# Fog_DRL_Cam.net
KiCad netlist of a schematic drawn in EAGLE
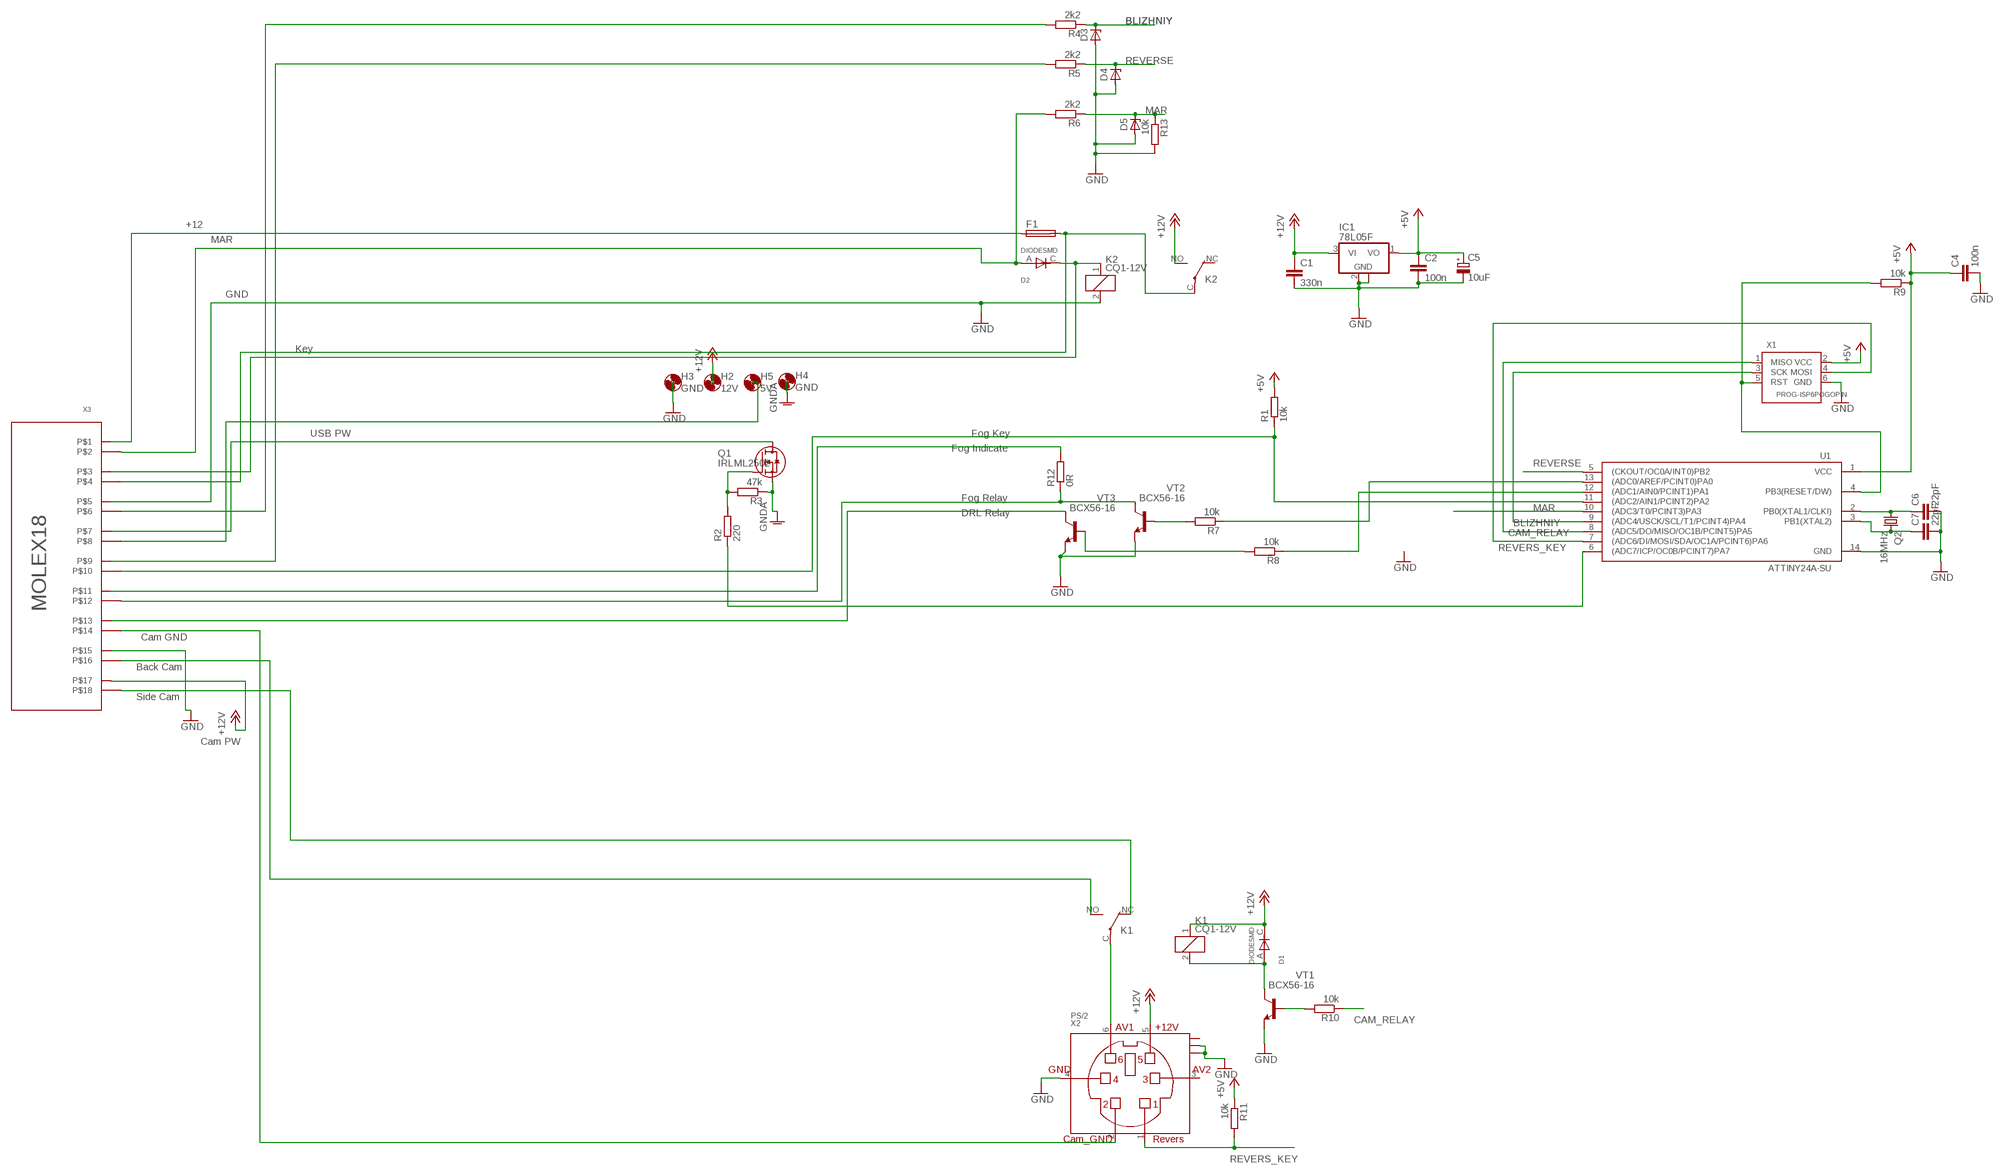
[diagram p0: schematic, sheet 1]

(export (version "E")
  (design (tool "Eeschema 10.0.6"))
  (components
    (comp (ref "C1")
      (value "330n")
      (footprint "eagle-import:C0805")
      (libsource (lib "eagle-import") (part "C-EUC0805"))
    )
    (comp (ref "C2")
      (value "100n")
      (footprint "eagle-import:C0603")
      (libsource (lib "eagle-import") (part "C-EUC0603"))
    )
    (comp (ref "C4")
      (value "100n")
      (footprint "eagle-import:C0603")
      (libsource (lib "eagle-import") (part "C-EUC0603"))
    )
    (comp (ref "C5")
      (value "10uF")
      (footprint "eagle-import:CT3216")
      (libsource (lib "eagle-import") (part "CPOL-EUCT3216"))
    )
    (comp (ref "C6")
      (value "22pF")
      (footprint "eagle-import:C0603")
      (libsource (lib "eagle-import") (part "rcl_334_C-EUC0603"))
    )
    (comp (ref "C7")
      (value "22pF")
      (footprint "eagle-import:C0603")
      (libsource (lib "eagle-import") (part "rcl_334_C-EUC0603"))
    )
    (comp (ref "D1")
      (value "DIODESMD")
      (footprint "eagle-import:DO214AC")
      (libsource (lib "eagle-import") (part "DIODESMD"))
    )
    (comp (ref "D2")
      (value "DIODESMD")
      (footprint "eagle-import:DO214AC")
      (libsource (lib "eagle-import") (part "DIODESMD"))
    )
    (comp (ref "D3")
      (value "ZENER-DIODESOD80C")
      (footprint "eagle-import:SOD80C")
      (libsource (lib "eagle-import") (part "ZENER-DIODESOD80C"))
    )
    (comp (ref "D4")
      (value "ZENER-DIODESOD80C")
      (footprint "eagle-import:SOD80C")
      (libsource (lib "eagle-import") (part "ZENER-DIODESOD80C"))
    )
    (comp (ref "D5")
      (value "ZENER-DIODESOD80C")
      (footprint "eagle-import:SOD80C")
      (libsource (lib "eagle-import") (part "ZENER-DIODESOD80C"))
    )
    (comp (ref "F1")
      (value "SH22,5A")
      (footprint "eagle-import:SH22,5A")
      (fields (field (name "MPN") "0031.7701.11"))
      (libsource (lib "eagle-import") (part "SH22,5A"))
    )
    (comp (ref "H2")
      (value "12V")
      (footprint "eagle-import:3,0")
      (libsource (lib "eagle-import") (part "MOUNT-HOLE3.0"))
    )
    (comp (ref "H3")
      (value "GND")
      (footprint "eagle-import:3,0")
      (libsource (lib "eagle-import") (part "MOUNT-HOLE3.0"))
    )
    (comp (ref "H4")
      (value "GND")
      (footprint "eagle-import:3,0")
      (libsource (lib "eagle-import") (part "MOUNT-HOLE3.0"))
    )
    (comp (ref "H5")
      (value "5V")
      (footprint "eagle-import:3,0")
      (libsource (lib "eagle-import") (part "MOUNT-HOLE3.0"))
    )
    (comp (ref "IC1")
      (value "78L05F")
      (footprint "eagle-import:SOT89")
      (libsource (lib "eagle-import") (part "78LF05"))
    )
    (comp (ref "K1")
      (value "CQ1-12V")
      (footprint "eagle-import:CQ1")
      (libsource (lib "eagle-import") (part "CQ1-12V"))
    )
    (comp (ref "K2")
      (value "CQ1-12V")
      (footprint "eagle-import:CQ1")
      (libsource (lib "eagle-import") (part "CQ1-12V"))
    )
    (comp (ref "Q1")
      (value "IRLML2502")
      (footprint "eagle-import:SOT-23-GSD")
      (libsource (lib "eagle-import") (part "SI2302"))
    )
    (comp (ref "Q2")
      (value "16MHz")
      (footprint "eagle-import:HC49_S")
      (libsource (lib "eagle-import") (part "CRYSTALHC49S"))
    )
    (comp (ref "R1")
      (value "10k")
      (footprint "eagle-import:R0603")
      (libsource (lib "eagle-import") (part "R-EU_R0603"))
    )
    (comp (ref "R2")
      (value "220")
      (footprint "eagle-import:R0603")
      (libsource (lib "eagle-import") (part "R-EU_R0603"))
    )
    (comp (ref "R3")
      (value "47k")
      (footprint "eagle-import:R0603")
      (libsource (lib "eagle-import") (part "R-EU_R0603"))
    )
    (comp (ref "R4")
      (value "2k2")
      (footprint "eagle-import:R0603")
      (libsource (lib "eagle-import") (part "R-EU_R0603"))
    )
    (comp (ref "R5")
      (value "2k2")
      (footprint "eagle-import:R0603")
      (libsource (lib "eagle-import") (part "R-EU_R0603"))
    )
    (comp (ref "R6")
      (value "2k2")
      (footprint "eagle-import:R0603")
      (libsource (lib "eagle-import") (part "R-EU_R0603"))
    )
    (comp (ref "R7")
      (value "10k")
      (footprint "eagle-import:R0603")
      (libsource (lib "eagle-import") (part "R-EU_R0603"))
    )
    (comp (ref "R8")
      (value "10k")
      (footprint "eagle-import:R0603")
      (libsource (lib "eagle-import") (part "R-EU_R0603"))
    )
    (comp (ref "R9")
      (value "10k")
      (footprint "eagle-import:R0603")
      (libsource (lib "eagle-import") (part "R-EU_R0603"))
    )
    (comp (ref "R10")
      (value "10k")
      (footprint "eagle-import:R0603")
      (libsource (lib "eagle-import") (part "R-EU_R0603"))
    )
    (comp (ref "R11")
      (value "10k")
      (footprint "eagle-import:R0603")
      (libsource (lib "eagle-import") (part "R-EU_R0603"))
    )
    (comp (ref "R12")
      (value "0R")
      (footprint "eagle-import:R0603")
      (libsource (lib "eagle-import") (part "R-EU_R0603"))
    )
    (comp (ref "R13")
      (value "10k")
      (footprint "eagle-import:R0603")
      (libsource (lib "eagle-import") (part "R-EU_R0603"))
    )
    (comp (ref "U1")
      (value "ATTINY24A-SU")
      (footprint "eagle-import:SO14")
      (libsource (lib "eagle-import") (part "ATTINY24A-SU"))
    )
    (comp (ref "VT1")
      (value "BCX56-16")
      (footprint "eagle-import:SOT89-BCE")
      (libsource (lib "eagle-import") (part "BCX56-16"))
    )
    (comp (ref "VT2")
      (value "BCX56-16")
      (footprint "eagle-import:SOT89-BCE")
      (libsource (lib "eagle-import") (part "BCX56-16"))
    )
    (comp (ref "VT3")
      (value "BCX56-16")
      (footprint "eagle-import:SOT89-BCE")
      (libsource (lib "eagle-import") (part "BCX56-16"))
    )
    (comp (ref "X1")
      (value "PROG-ISP6POGOPIN")
      (footprint "eagle-import:PROG_POGOPIN")
      (libsource (lib "eagle-import") (part "PROG-ISP6POGOPIN"))
    )
    (comp (ref "X2")
      (value "PS/2")
      (footprint "eagle-import:PS_2")
      (libsource (lib "eagle-import") (part "PS/2"))
    )
    (comp (ref "X3")
      (value "MOLEX18")
      (footprint "eagle-import:MOLEX18")
      (libsource (lib "eagle-import") (part "MOLEX18"))
    )
  )
  (nets
    (net (code "1") (name "+5V") (class "Default")
      (node (ref "C2") (pin "1") (pinfunction "1_1") (pintype "passive"))
      (node (ref "C4") (pin "1") (pinfunction "1_1") (pintype "passive"))
      (node (ref "C5") (pin "+") (pinfunction "+_+") (pintype "passive"))
      (node (ref "IC1") (pin "1") (pinfunction "VO_1") (pintype "passive"))
      (node (ref "R1") (pin "2") (pinfunction "2_2") (pintype "passive"))
      (node (ref "R11") (pin "1") (pinfunction "1_1") (pintype "passive"))
      (node (ref "R9") (pin "1") (pinfunction "1_1") (pintype "passive"))
      (node (ref "U1") (pin "1") (pinfunction "VCC_1") (pintype "power_in"))
      (node (ref "X1") (pin "2") (pinfunction "VCC_2") (pintype "bidirectional"))
    )
    (net (code "2") (name "+12V") (class "Default")
      (node (ref "C1") (pin "1") (pinfunction "1_1") (pintype "passive"))
      (node (ref "D1") (pin "C") (pinfunction "KATOD_C") (pintype "power_in"))
      (node (ref "H2") (pin "P$1") (pinfunction "P$1_P$1") (pintype "bidirectional"))
      (node (ref "IC1") (pin "3") (pinfunction "VI_3") (pintype "input"))
      (node (ref "K1") (pin "1") (pinfunction "1_1") (pintype "passive"))
      (node (ref "K2") (pin "NO") (pinfunction "S_NO") (pintype "passive"))
      (node (ref "X2") (pin "5") (pinfunction "5_5") (pintype "bidirectional"))
      (node (ref "X3") (pin "P$17") (pinfunction "P$17_P$17") (pintype "bidirectional"))
    )
    (net (code "3") (name "/BLIZHNIY") (class "Default")
      (node (ref "D3") (pin "C") (pinfunction "C_C") (pintype "passive"))
      (node (ref "R4") (pin "1") (pinfunction "1_1") (pintype "passive"))
      (node (ref "U1") (pin "9") (pinfunction "(ADC4/USCK/SCL/T1/PCINT4)PA4_9") (pintype "bidirectional"))
      (node (ref "X1") (pin "3") (pinfunction "SCK_3") (pintype "bidirectional"))
    )
    (net (code "4") (name "/CAM_RELAY") (class "Default")
      (node (ref "R10") (pin "1") (pinfunction "1_1") (pintype "passive"))
      (node (ref "U1") (pin "8") (pinfunction "(ADC5/DO/MISO/OC1B/PCINT5)PA5_8") (pintype "bidirectional"))
      (node (ref "X1") (pin "1") (pinfunction "MISO_1") (pintype "bidirectional"))
    )
    (net (code "5") (name "/MAR") (class "Default")
      (node (ref "D5") (pin "C") (pinfunction "C_C") (pintype "passive"))
      (node (ref "R13") (pin "1") (pinfunction "1_1") (pintype "passive"))
      (node (ref "R6") (pin "1") (pinfunction "1_1") (pintype "passive"))
      (node (ref "U1") (pin "10") (pinfunction "(ADC3/T0/PCINT3)PA3_10") (pintype "bidirectional"))
    )
    (net (code "6") (name "/REVERSE") (class "Default")
      (node (ref "D4") (pin "C") (pinfunction "C_C") (pintype "passive"))
      (node (ref "R5") (pin "1") (pinfunction "1_1") (pintype "passive"))
      (node (ref "U1") (pin "5") (pinfunction "(CKOUT/OC0A/INT0)PB2_5") (pintype "bidirectional"))
    )
    (net (code "7") (name "/REVERS_KEY") (class "Default")
      (node (ref "R11") (pin "2") (pinfunction "2_2") (pintype "passive"))
      (node (ref "U1") (pin "7") (pinfunction "(ADC6/DI/MOSI/SDA/OC1A/PCINT6)PA6_7") (pintype "bidirectional"))
      (node (ref "X1") (pin "4") (pinfunction "MOSI_4") (pintype "bidirectional"))
      (node (ref "X2") (pin "1") (pinfunction "1_1") (pintype "bidirectional"))
    )
    (net (code "8") (name "GND") (class "Default")
      (node (ref "C1") (pin "2") (pinfunction "2_2") (pintype "passive"))
      (node (ref "C2") (pin "2") (pinfunction "2_2") (pintype "passive"))
      (node (ref "C4") (pin "2") (pinfunction "2_2") (pintype "passive"))
      (node (ref "C5") (pin "-") (pinfunction "-_-") (pintype "passive"))
      (node (ref "C6") (pin "2") (pinfunction "2_2") (pintype "passive"))
      (node (ref "C7") (pin "2") (pinfunction "2_2") (pintype "passive"))
      (node (ref "D3") (pin "A") (pinfunction "A_A") (pintype "passive"))
      (node (ref "D4") (pin "A") (pinfunction "A_A") (pintype "passive"))
      (node (ref "D5") (pin "A") (pinfunction "A_A") (pintype "passive"))
      (node (ref "H3") (pin "P$1") (pinfunction "P$1_P$1") (pintype "bidirectional"))
      (node (ref "IC1") (pin "2") (pinfunction "GND_2") (pintype "passive"))
      (node (ref "IC1") (pin "2@1") (pinfunction "GND_2@1") (pintype "passive"))
      (node (ref "K2") (pin "2") (pinfunction "2_2") (pintype "passive"))
      (node (ref "R13") (pin "2") (pinfunction "2_2") (pintype "passive"))
      (node (ref "U1") (pin "14") (pinfunction "GND_14") (pintype "power_in"))
      (node (ref "VT1") (pin "E") (pinfunction "E_E") (pintype "passive"))
      (node (ref "VT2") (pin "E") (pinfunction "E_E") (pintype "passive"))
      (node (ref "VT3") (pin "E") (pinfunction "E_E") (pintype "passive"))
      (node (ref "X1") (pin "6") (pinfunction "GND_6") (pintype "power_in"))
      (node (ref "X2") (pin "4") (pinfunction "4_4") (pintype "bidirectional"))
      (node (ref "X2") (pin "GND0") (pinfunction "GND0_GND0") (pintype "bidirectional"))
      (node (ref "X2") (pin "GND2") (pinfunction "GND2_GND2") (pintype "bidirectional"))
      (node (ref "X3") (pin "P$15") (pinfunction "P$15_P$15") (pintype "bidirectional"))
      (node (ref "X3") (pin "P$5") (pinfunction "P$5_P$5") (pintype "bidirectional"))
    )
    (net (code "9") (name "GNDA") (class "Default")
      (node (ref "H4") (pin "P$1") (pinfunction "P$1_P$1") (pintype "bidirectional"))
      (node (ref "Q1") (pin "S") (pinfunction "S_S") (pintype "passive"))
      (node (ref "R3") (pin "1") (pinfunction "1_1") (pintype "passive"))
    )
    (net (code "10") (name "Net-(D1-ANOD)") (class "Default")
      (node (ref "D1") (pin "A") (pinfunction "ANOD_A") (pintype "power_in"))
      (node (ref "K1") (pin "2") (pinfunction "2_2") (pintype "passive"))
      (node (ref "VT1") (pin "C") (pinfunction "C_C") (pintype "passive"))
      (node (ref "VT1") (pin "C@1") (pinfunction "C_C@1") (pintype "passive"))
    )
    (net (code "11") (name "Net-(D2-ANOD)") (class "Default")
      (node (ref "D2") (pin "A") (pinfunction "ANOD_A") (pintype "power_in"))
      (node (ref "R6") (pin "2") (pinfunction "2_2") (pintype "passive"))
      (node (ref "X3") (pin "P$2") (pinfunction "P$2_P$2") (pintype "bidirectional"))
    )
    (net (code "12") (name "Net-(D2-KATOD)") (class "Default")
      (node (ref "D2") (pin "C") (pinfunction "KATOD_C") (pintype "power_in"))
      (node (ref "K2") (pin "1") (pinfunction "1_1") (pintype "passive"))
      (node (ref "X3") (pin "P$3") (pinfunction "P$3_P$3") (pintype "bidirectional"))
    )
    (net (code "13") (name "Net-(F1-Pad1)") (class "Default")
      (node (ref "F1") (pin "1") (pinfunction "1_1") (pintype "passive"))
      (node (ref "X3") (pin "P$1") (pinfunction "P$1_P$1") (pintype "bidirectional"))
    )
    (net (code "14") (name "Net-(H5-PadP$1)") (class "Default")
      (node (ref "H5") (pin "P$1") (pinfunction "P$1_P$1") (pintype "bidirectional"))
      (node (ref "X3") (pin "P$8") (pinfunction "P$8_P$8") (pintype "bidirectional"))
    )
    (net (code "15") (name "Net-(K1B-O)") (class "Default")
      (node (ref "K1") (pin "NC") (pinfunction "O_NC") (pintype "passive"))
      (node (ref "X3") (pin "P$18") (pinfunction "P$18_P$18") (pintype "bidirectional"))
    )
    (net (code "16") (name "Net-(K1B-P)") (class "Default")
      (node (ref "K1") (pin "C") (pinfunction "P_C") (pintype "passive"))
      (node (ref "X2") (pin "6") (pinfunction "6_6") (pintype "bidirectional"))
    )
    (net (code "17") (name "Net-(K1B-S)") (class "Default")
      (node (ref "K1") (pin "NO") (pinfunction "S_NO") (pintype "passive"))
      (node (ref "X3") (pin "P$16") (pinfunction "P$16_P$16") (pintype "bidirectional"))
    )
    (net (code "18") (name "Net-(K2B-P)") (class "Default")
      (node (ref "F1") (pin "2") (pinfunction "2_2") (pintype "passive"))
      (node (ref "K2") (pin "C") (pinfunction "P_C") (pintype "passive"))
      (node (ref "X3") (pin "P$4") (pinfunction "P$4_P$4") (pintype "bidirectional"))
    )
    (net (code "19") (name "Net-(Q1-PadD)") (class "Default")
      (node (ref "Q1") (pin "D") (pinfunction "D_D") (pintype "passive"))
      (node (ref "X3") (pin "P$7") (pinfunction "P$7_P$7") (pintype "bidirectional"))
    )
    (net (code "20") (name "Net-(Q1-PadG)") (class "Default")
      (node (ref "Q1") (pin "G") (pinfunction "G_G") (pintype "passive"))
      (node (ref "R2") (pin "2") (pinfunction "2_2") (pintype "passive"))
      (node (ref "R3") (pin "2") (pinfunction "2_2") (pintype "passive"))
    )
    (net (code "21") (name "Net-(R4-Pad2)") (class "Default")
      (node (ref "R4") (pin "2") (pinfunction "2_2") (pintype "passive"))
      (node (ref "X3") (pin "P$6") (pinfunction "P$6_P$6") (pintype "bidirectional"))
    )
    (net (code "22") (name "Net-(R5-Pad2)") (class "Default")
      (node (ref "R5") (pin "2") (pinfunction "2_2") (pintype "passive"))
      (node (ref "X3") (pin "P$9") (pinfunction "P$9_P$9") (pintype "bidirectional"))
    )
    (net (code "23") (name "Net-(R7-Pad2)") (class "Default")
      (node (ref "R7") (pin "2") (pinfunction "2_2") (pintype "passive"))
      (node (ref "VT2") (pin "B") (pinfunction "B_B") (pintype "passive"))
    )
    (net (code "24") (name "Net-(R8-Pad2)") (class "Default")
      (node (ref "R8") (pin "2") (pinfunction "2_2") (pintype "passive"))
      (node (ref "VT3") (pin "B") (pinfunction "B_B") (pintype "passive"))
    )
    (net (code "25") (name "Net-(R10-Pad2)") (class "Default")
      (node (ref "R10") (pin "2") (pinfunction "2_2") (pintype "passive"))
      (node (ref "VT1") (pin "B") (pinfunction "B_B") (pintype "passive"))
    )
    (net (code "26") (name "Net-(R12-Pad1)") (class "Default")
      (node (ref "R12") (pin "1") (pinfunction "1_1") (pintype "passive"))
      (node (ref "VT2") (pin "C") (pinfunction "C_C") (pintype "passive"))
      (node (ref "VT2") (pin "C@1") (pinfunction "C_C@1") (pintype "passive"))
      (node (ref "X3") (pin "P$12") (pinfunction "P$12_P$12") (pintype "bidirectional"))
    )
    (net (code "27") (name "Net-(R12-Pad2)") (class "Default")
      (node (ref "R12") (pin "2") (pinfunction "2_2") (pintype "passive"))
      (node (ref "X3") (pin "P$11") (pinfunction "P$11_P$11") (pintype "bidirectional"))
    )
    (net (code "28") (name "Net-(U1-(ADC0{slash}AREF{slash}PCINT0)PA0)") (class "Default")
      (node (ref "R7") (pin "1") (pinfunction "1_1") (pintype "passive"))
      (node (ref "U1") (pin "13") (pinfunction "(ADC0/AREF/PCINT0)PA0_13") (pintype "bidirectional"))
    )
    (net (code "29") (name "Net-(U1-(ADC1{slash}AIN0{slash}PCINT1)PA1)") (class "Default")
      (node (ref "R8") (pin "1") (pinfunction "1_1") (pintype "passive"))
      (node (ref "U1") (pin "12") (pinfunction "(ADC1/AIN0/PCINT1)PA1_12") (pintype "bidirectional"))
    )
    (net (code "30") (name "Net-(U1-(ADC2{slash}AIN1{slash}PCINT2)PA2)") (class "Default")
      (node (ref "R1") (pin "1") (pinfunction "1_1") (pintype "passive"))
      (node (ref "U1") (pin "11") (pinfunction "(ADC2/AIN1/PCINT2)PA2_11") (pintype "bidirectional"))
      (node (ref "X3") (pin "P$10") (pinfunction "P$10_P$10") (pintype "bidirectional"))
    )
    (net (code "31") (name "Net-(U1-(ADC7{slash}ICP{slash}OC0B{slash}PCINT7)PA7)") (class "Default")
      (node (ref "R2") (pin "1") (pinfunction "1_1") (pintype "passive"))
      (node (ref "U1") (pin "6") (pinfunction "(ADC7/ICP/OC0B/PCINT7)PA7_6") (pintype "bidirectional"))
    )
    (net (code "32") (name "Net-(U1-PB0(XTAL1{slash}CLKI))") (class "Default")
      (node (ref "C6") (pin "1") (pinfunction "1_1") (pintype "passive"))
      (node (ref "Q2") (pin "1") (pinfunction "1_1") (pintype "passive"))
      (node (ref "U1") (pin "2") (pinfunction "PB0(XTAL1/CLKI)_2") (pintype "bidirectional"))
    )
    (net (code "33") (name "Net-(U1-PB1(XTAL2))") (class "Default")
      (node (ref "C7") (pin "1") (pinfunction "1_1") (pintype "passive"))
      (node (ref "Q2") (pin "2") (pinfunction "2_2") (pintype "passive"))
      (node (ref "U1") (pin "3") (pinfunction "PB1(XTAL2)_3") (pintype "bidirectional"))
    )
    (net (code "34") (name "Net-(U1-PB3(RESET{slash}DW))") (class "Default")
      (node (ref "R9") (pin "2") (pinfunction "2_2") (pintype "passive"))
      (node (ref "U1") (pin "4") (pinfunction "PB3(RESET/DW)_4") (pintype "bidirectional"))
      (node (ref "X1") (pin "5") (pinfunction "RST_5") (pintype "bidirectional"))
    )
    (net (code "35") (name "Net-(VT3-C-PadC@1)") (class "Default")
      (node (ref "VT3") (pin "C") (pinfunction "C_C") (pintype "passive"))
      (node (ref "VT3") (pin "C@1") (pinfunction "C_C@1") (pintype "passive"))
      (node (ref "X3") (pin "P$13") (pinfunction "P$13_P$13") (pintype "bidirectional"))
    )
    (net (code "36") (name "Net-(X2-Pad2)") (class "Default")
      (node (ref "X2") (pin "2") (pinfunction "2_2") (pintype "bidirectional"))
      (node (ref "X3") (pin "P$14") (pinfunction "P$14_P$14") (pintype "bidirectional"))
    )
    (net (code "37") (name "unconnected-(K2B-O-PadNC)") (class "Default")
      (node (ref "K2") (pin "NC") (pinfunction "O_NC") (pintype "passive"))
    )
    (net (code "38") (name "unconnected-(X2-Pad3)") (class "Default")
      (node (ref "X2") (pin "3") (pinfunction "3_3") (pintype "bidirectional"))
    )
    (net (code "39") (name "unconnected-(X2-PadGND1)") (class "Default")
      (node (ref "X2") (pin "GND1") (pinfunction "GND1_GND1") (pintype "bidirectional"))
    )
  )
)
